# 2024-10-30.net
KiCad netlist of a schematic drawn in Altium Designer
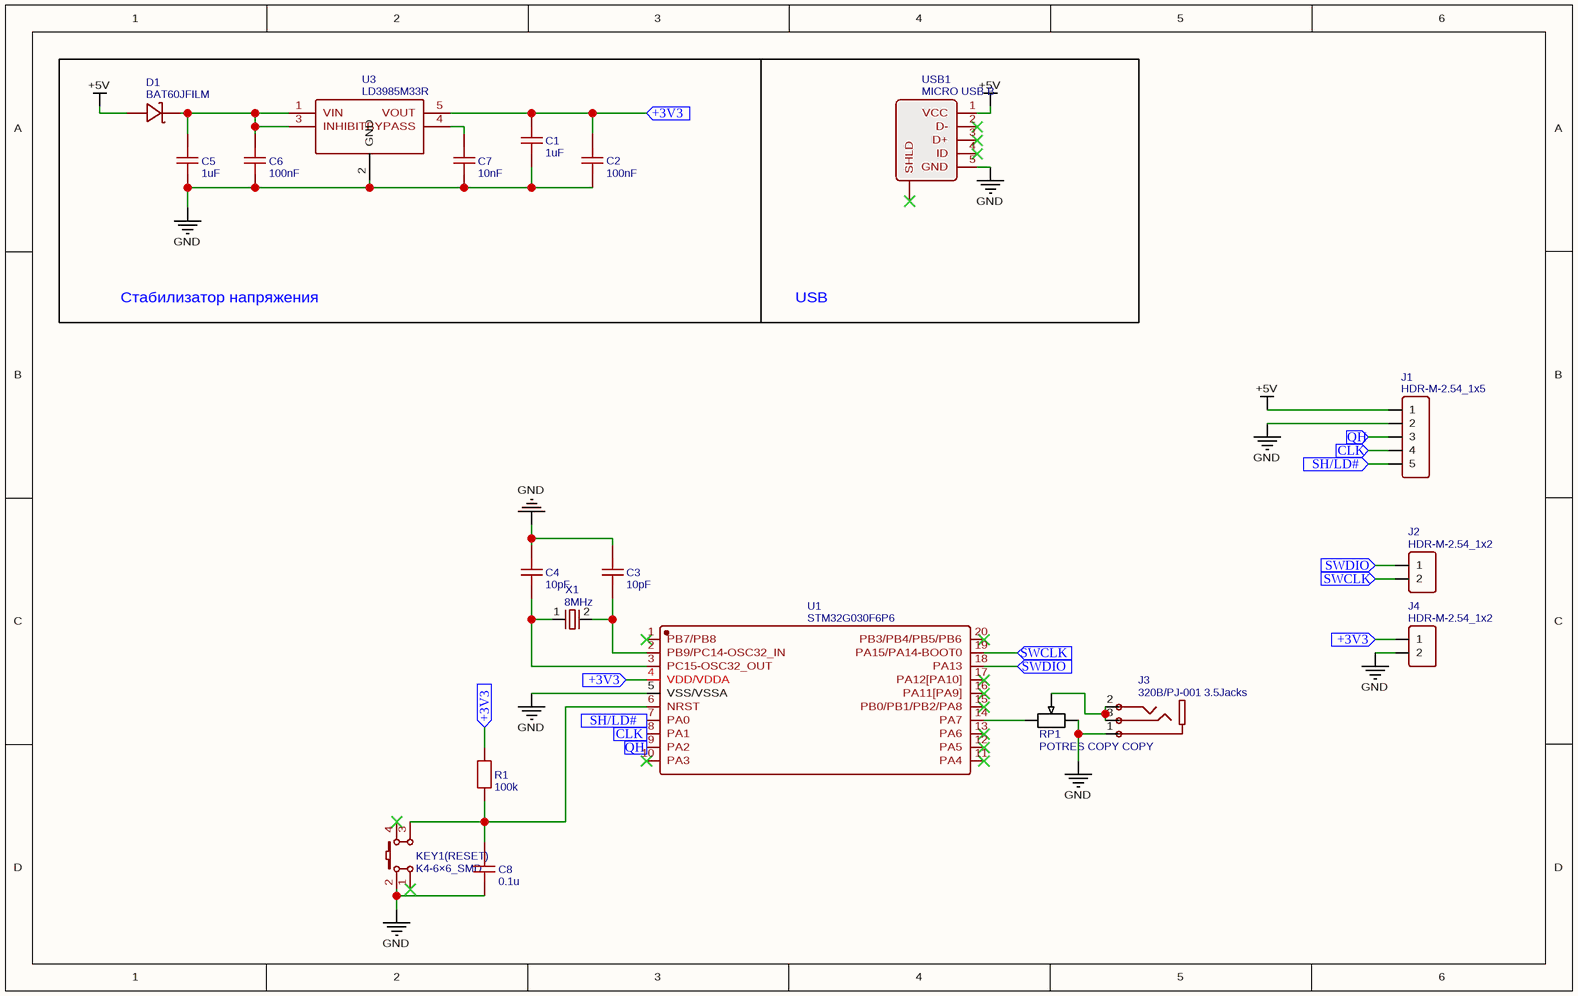
[diagram p0: Микроконтроллер_2024-10-30.schdoc]

(export (version "E")
  (design (tool "Eeschema 10.0.6"))
  (components
    (comp (ref "C1")
      (value "1uF")
      (fields (field (name "CONTRIBUTOR") "LCEDA_Lib"))
      (libsource (lib "altium-import") (part "root_1_1uF_"))
    )
    (comp (ref "C2")
      (value "100nF")
      (fields (field (name "CONTRIBUTOR") "LCEDA_Lib"))
      (libsource (lib "altium-import") (part "root_1_100nF_"))
    )
    (comp (ref "C3")
      (value "10pF")
      (fields (field (name "CONTRIBUTOR") "LCEDA_Lib"))
      (libsource (lib "altium-import") (part "root_3_10pF_"))
    )
    (comp (ref "C4")
      (value "10pF")
      (fields (field (name "CONTRIBUTOR") "LCEDA_Lib"))
      (libsource (lib "altium-import") (part "root_3_10pF_"))
    )
    (comp (ref "C5")
      (value "1uF")
      (fields (field (name "CONTRIBUTOR") "LCEDA_Lib"))
      (libsource (lib "altium-import") (part "root_1_1uF_"))
    )
    (comp (ref "C6")
      (value "100nF")
      (fields (field (name "CONTRIBUTOR") "LCEDA_Lib"))
      (libsource (lib "altium-import") (part "root_1_100nF_"))
    )
    (comp (ref "C7")
      (value "10nF")
      (fields (field (name "CONTRIBUTOR") "LCEDA_Lib"))
      (libsource (lib "altium-import") (part "root_1_10nF_"))
    )
    (comp (ref "C8")
      (value "0.1u")
      (fields (field (name "CONTRIBUTOR") "LCEDA_Lib"))
      (libsource (lib "altium-import") (part "root_1_0.1u_"))
    )
    (comp (ref "D1")
      (value "BAT60JFILM")
      (fields (field (name "MANUFACTURER") "ST(意法半导体)") (field (name "CONTRIBUTOR") "LCSC"))
      (libsource (lib "altium-import") (part "root_2_BAT60JFILM_"))
    )
    (comp (ref "J1")
      (value "HDR-M-2.54_1x5")
      (fields (field (name "CONTRIBUTOR") "LCEDA_Lib"))
      (libsource (lib "altium-import") (part "root_0_HDR-M-2.54_1x5_"))
    )
    (comp (ref "J2")
      (value "HDR-M-2.54_1x2")
      (fields (field (name "CONTRIBUTOR") "LCEDA_Lib"))
      (libsource (lib "altium-import") (part "root_0_HDR-M-2.54_1x2_"))
    )
    (comp (ref "J3")
      (value "320B/PJ-001 3.5Jacks")
      (fields (field (name "MANUFACTURER") "ReliaPro"))
      (libsource (lib "altium-import") (part "root_2_320B/PJ-001 3.5Jacks_"))
    )
    (comp (ref "J4")
      (value "HDR-M-2.54_1x2")
      (fields (field (name "CONTRIBUTOR") "LCEDA_Lib"))
      (libsource (lib "altium-import") (part "root_0_HDR-M-2.54_1x2_"))
    )
    (comp (ref "KEY1(RESET)")
      (value "K4-6×6_SMD")
      (fields
        (field (name "MANUFACTURER") "韩国韩荣")
        (field (name "MANUFACTURER PART") "K2-6639SP-D4SC-04")
        (field (name "CONTRIBUTOR") "LCEDA_Lib")
      )
      (libsource (lib "altium-import") (part "root_1_K4-6×6_SMD_"))
    )
    (comp (ref "R1")
      (value "100k")
      (fields (field (name "CONTRIBUTOR") "LCEDA_Lib"))
      (libsource (lib "altium-import") (part "root_1_100k_"))
    )
    (comp (ref "RP1")
      (value "POTRES COPY COPY")
      (fields (field (name "CONTRIBUTOR") "ttnigmatyllin"))
      (libsource (lib "altium-import") (part "root_0_POTRES COPY COPY_"))
    )
    (comp (ref "U1")
      (value "STM32G030F6P6")
      (fields (field (name "MANUFACTURER") "ST(意法半导体)") (field (name "CONTRIBUTOR") "LCSC"))
      (libsource (lib "altium-import") (part "root_0_STM32G030F6P6_"))
    )
    (comp (ref "U3")
      (value "LD3985M33R")
      (fields (field (name "MANUFACTURER") "ST(意法半导体)"))
      (libsource (lib "altium-import") (part "root_0_LD3985M33R_"))
    )
    (comp (ref "USB1")
      (value "MICRO USB B")
      (fields (field (name "MANUFACTURER") "HRO") (field (name "MANUFACTURER PART") "U-F-M5SW-Y-3"))
      (libsource (lib "altium-import") (part "root_0_MICRO USB B_"))
    )
    (comp (ref "X1")
      (value "8MHz")
      (fields
        (field (name "MANUFACTURER") "NDK")
        (field (name "MANUFACTURER PART") "NX3225GD-8MHZ-STD-CRA-3")
        (field (name "CONTRIBUTOR") "LCSC")
      )
      (libsource (lib "altium-import") (part "root_0_8MHz_"))
    )
  )
  (nets
    (net (code "1") (name "+5V") (class "Default")
      (node (ref "D1") (pin "2") (pinfunction "A_2") (pintype "passive"))
      (node (ref "J1") (pin "1") (pinfunction "1_1") (pintype "passive"))
      (node (ref "USB1") (pin "1") (pinfunction "VCC_1") (pintype "passive"))
    )
    (net (code "2") (name "/+3V3") (class "Default")
      (node (ref "C1") (pin "2") (pinfunction "2_2") (pintype "passive"))
      (node (ref "C2") (pin "2") (pinfunction "2_2") (pintype "passive"))
      (node (ref "J4") (pin "1") (pinfunction "1_1") (pintype "passive"))
      (node (ref "R1") (pin "2") (pinfunction "2_2") (pintype "passive"))
      (node (ref "U1") (pin "4") (pinfunction "VDD/VDDA_4") (pintype "passive"))
      (node (ref "U3") (pin "5") (pinfunction "VOUT_5") (pintype "passive"))
    )
    (net (code "3") (name "/CLK") (class "Default")
      (node (ref "J1") (pin "4") (pinfunction "4_4") (pintype "passive"))
      (node (ref "U1") (pin "8") (pinfunction "PA1_8") (pintype "passive"))
    )
    (net (code "4") (name "/QH") (class "Default")
      (node (ref "J1") (pin "3") (pinfunction "3_3") (pintype "passive"))
      (node (ref "U1") (pin "9") (pinfunction "PA2_9") (pintype "passive"))
    )
    (net (code "5") (name "/SH{slash}LD#") (class "Default")
      (node (ref "J1") (pin "5") (pinfunction "5_5") (pintype "passive"))
      (node (ref "U1") (pin "7") (pinfunction "PA0_7") (pintype "passive"))
    )
    (net (code "6") (name "/SWCLK") (class "Default")
      (node (ref "J2") (pin "2") (pinfunction "2_2") (pintype "passive"))
      (node (ref "U1") (pin "19") (pinfunction "PA15/PA14-BOOT0_19") (pintype "passive"))
    )
    (net (code "7") (name "/SWDIO") (class "Default")
      (node (ref "J2") (pin "1") (pinfunction "1_1") (pintype "passive"))
      (node (ref "U1") (pin "18") (pinfunction "PA13_18") (pintype "passive"))
    )
    (net (code "8") (name "GND") (class "Default")
      (node (ref "C1") (pin "1") (pinfunction "1_1") (pintype "passive"))
      (node (ref "C2") (pin "1") (pinfunction "1_1") (pintype "passive"))
      (node (ref "C3") (pin "1") (pinfunction "1_1") (pintype "passive"))
      (node (ref "C4") (pin "1") (pinfunction "1_1") (pintype "passive"))
      (node (ref "C5") (pin "1") (pinfunction "1_1") (pintype "passive"))
      (node (ref "C6") (pin "1") (pinfunction "1_1") (pintype "passive"))
      (node (ref "C7") (pin "1") (pinfunction "1_1") (pintype "passive"))
      (node (ref "C8") (pin "1") (pinfunction "1_1") (pintype "passive"))
      (node (ref "J1") (pin "2") (pinfunction "2_2") (pintype "passive"))
      (node (ref "J3") (pin "1") (pinfunction "1_1") (pintype "passive"))
      (node (ref "J4") (pin "2") (pinfunction "2_2") (pintype "passive"))
      (node (ref "KEY1(RESET)") (pin "2") (pinfunction "2_2") (pintype "passive"))
      (node (ref "RP1") (pin "3") (pinfunction "3_3") (pintype "passive"))
      (node (ref "U1") (pin "5") (pinfunction "VSS/VSSA_5") (pintype "passive"))
      (node (ref "U3") (pin "2") (pinfunction "GND_2") (pintype "passive"))
      (node (ref "USB1") (pin "5") (pinfunction "GND_5") (pintype "passive"))
    )
    (net (code "9") (name "Net-(D1-K)") (class "Default")
      (node (ref "C5") (pin "2") (pinfunction "2_2") (pintype "passive"))
      (node (ref "C6") (pin "2") (pinfunction "2_2") (pintype "passive"))
      (node (ref "D1") (pin "1") (pinfunction "K_1") (pintype "passive"))
      (node (ref "U3") (pin "1") (pinfunction "VIN_1") (pintype "passive"))
      (node (ref "U3") (pin "3") (pinfunction "INHIBIT_3") (pintype "passive"))
    )
    (net (code "10") (name "Net-(J3-Pad2)") (class "Default")
      (node (ref "J3") (pin "2") (pinfunction "2_2") (pintype "passive"))
      (node (ref "J3") (pin "3") (pinfunction "3_3") (pintype "passive"))
      (node (ref "RP1") (pin "2") (pinfunction "2_2") (pintype "passive"))
    )
    (net (code "11") (name "Net-(U1-NRST)") (class "Default")
      (node (ref "C8") (pin "2") (pinfunction "2_2") (pintype "passive"))
      (node (ref "KEY1(RESET)") (pin "3") (pinfunction "3_3") (pintype "passive"))
      (node (ref "R1") (pin "1") (pinfunction "1_1") (pintype "passive"))
      (node (ref "U1") (pin "6") (pinfunction "NRST_6") (pintype "passive"))
    )
    (net (code "12") (name "Net-(U1-PA7)") (class "Default")
      (node (ref "RP1") (pin "1") (pinfunction "1_1") (pintype "passive"))
      (node (ref "U1") (pin "14") (pinfunction "PA7_14") (pintype "passive"))
    )
    (net (code "13") (name "Net-(U1-PB9{slash}PC14-OSC32_IN)") (class "Default")
      (node (ref "C3") (pin "2") (pinfunction "2_2") (pintype "passive"))
      (node (ref "U1") (pin "2") (pinfunction "PB9/PC14-OSC32_IN_2") (pintype "passive"))
      (node (ref "X1") (pin "2") (pinfunction "GND_2") (pintype "passive"))
    )
    (net (code "14") (name "Net-(U1-PC15-OSC32_OUT)") (class "Default")
      (node (ref "C4") (pin "2") (pinfunction "2_2") (pintype "passive"))
      (node (ref "U1") (pin "3") (pinfunction "PC15-OSC32_OUT_3") (pintype "passive"))
      (node (ref "X1") (pin "1") (pinfunction "1_1") (pintype "passive"))
    )
    (net (code "15") (name "Net-(U3-BYPASS)") (class "Default")
      (node (ref "C7") (pin "2") (pinfunction "2_2") (pintype "passive"))
      (node (ref "U3") (pin "4") (pinfunction "BYPASS_4") (pintype "passive"))
    )
    (net (code "16") (name "unconnected-(KEY1(RESET)-Pad1)") (class "Default")
      (node (ref "KEY1(RESET)") (pin "1") (pinfunction "1_1") (pintype "passive+no_connect"))
    )
    (net (code "17") (name "unconnected-(KEY1(RESET)-Pad4)") (class "Default")
      (node (ref "KEY1(RESET)") (pin "4") (pinfunction "4_4") (pintype "passive+no_connect"))
    )
    (net (code "18") (name "unconnected-(U1-PA3-Pad10)") (class "Default")
      (node (ref "U1") (pin "10") (pinfunction "PA3_10") (pintype "passive+no_connect"))
    )
    (net (code "19") (name "unconnected-(U1-PA4-Pad11)") (class "Default")
      (node (ref "U1") (pin "11") (pinfunction "PA4_11") (pintype "passive+no_connect"))
    )
    (net (code "20") (name "unconnected-(U1-PA5-Pad12)") (class "Default")
      (node (ref "U1") (pin "12") (pinfunction "PA5_12") (pintype "passive+no_connect"))
    )
    (net (code "21") (name "unconnected-(U1-PA6-Pad13)") (class "Default")
      (node (ref "U1") (pin "13") (pinfunction "PA6_13") (pintype "passive+no_connect"))
    )
    (net (code "22") (name "unconnected-(U1-PA11[PA9]-Pad16)") (class "Default")
      (node (ref "U1") (pin "16") (pinfunction "PA11[PA9]_16") (pintype "passive+no_connect"))
    )
    (net (code "23") (name "unconnected-(U1-PA12[PA10]-Pad17)") (class "Default")
      (node (ref "U1") (pin "17") (pinfunction "PA12[PA10]_17") (pintype "passive+no_connect"))
    )
    (net (code "24") (name "unconnected-(U1-PB0{slash}PB1{slash}PB2{slash}PA8-Pad15)") (class "Default")
      (node (ref "U1") (pin "15") (pinfunction "PB0/PB1/PB2/PA8_15") (pintype "passive+no_connect"))
    )
    (net (code "25") (name "unconnected-(U1-PB3{slash}PB4{slash}PB5{slash}PB6-Pad20)") (class "Default")
      (node (ref "U1") (pin "20") (pinfunction "PB3/PB4/PB5/PB6_20") (pintype "passive+no_connect"))
    )
    (net (code "26") (name "unconnected-(U1-PB7{slash}PB8-Pad1)") (class "Default")
      (node (ref "U1") (pin "1") (pinfunction "PB7/PB8_1") (pintype "passive+no_connect"))
    )
    (net (code "27") (name "unconnected-(USB1-D+-Pad3)") (class "Default")
      (node (ref "USB1") (pin "3") (pinfunction "D+_3") (pintype "passive+no_connect"))
    )
    (net (code "28") (name "unconnected-(USB1-D--Pad2)") (class "Default")
      (node (ref "USB1") (pin "2") (pinfunction "D-_2") (pintype "passive+no_connect"))
    )
    (net (code "29") (name "unconnected-(USB1-ID-Pad4)") (class "Default")
      (node (ref "USB1") (pin "4") (pinfunction "ID_4") (pintype "passive+no_connect"))
    )
    (net (code "30") (name "unconnected-(USB1-SHLD-Pad6)") (class "Default")
      (node (ref "USB1") (pin "6") (pinfunction "SHLD_6") (pintype "passive+no_connect"))
    )
  )
)
